# tempmontoring.net
KiCad netlist of a schematic drawn in Altium Designer
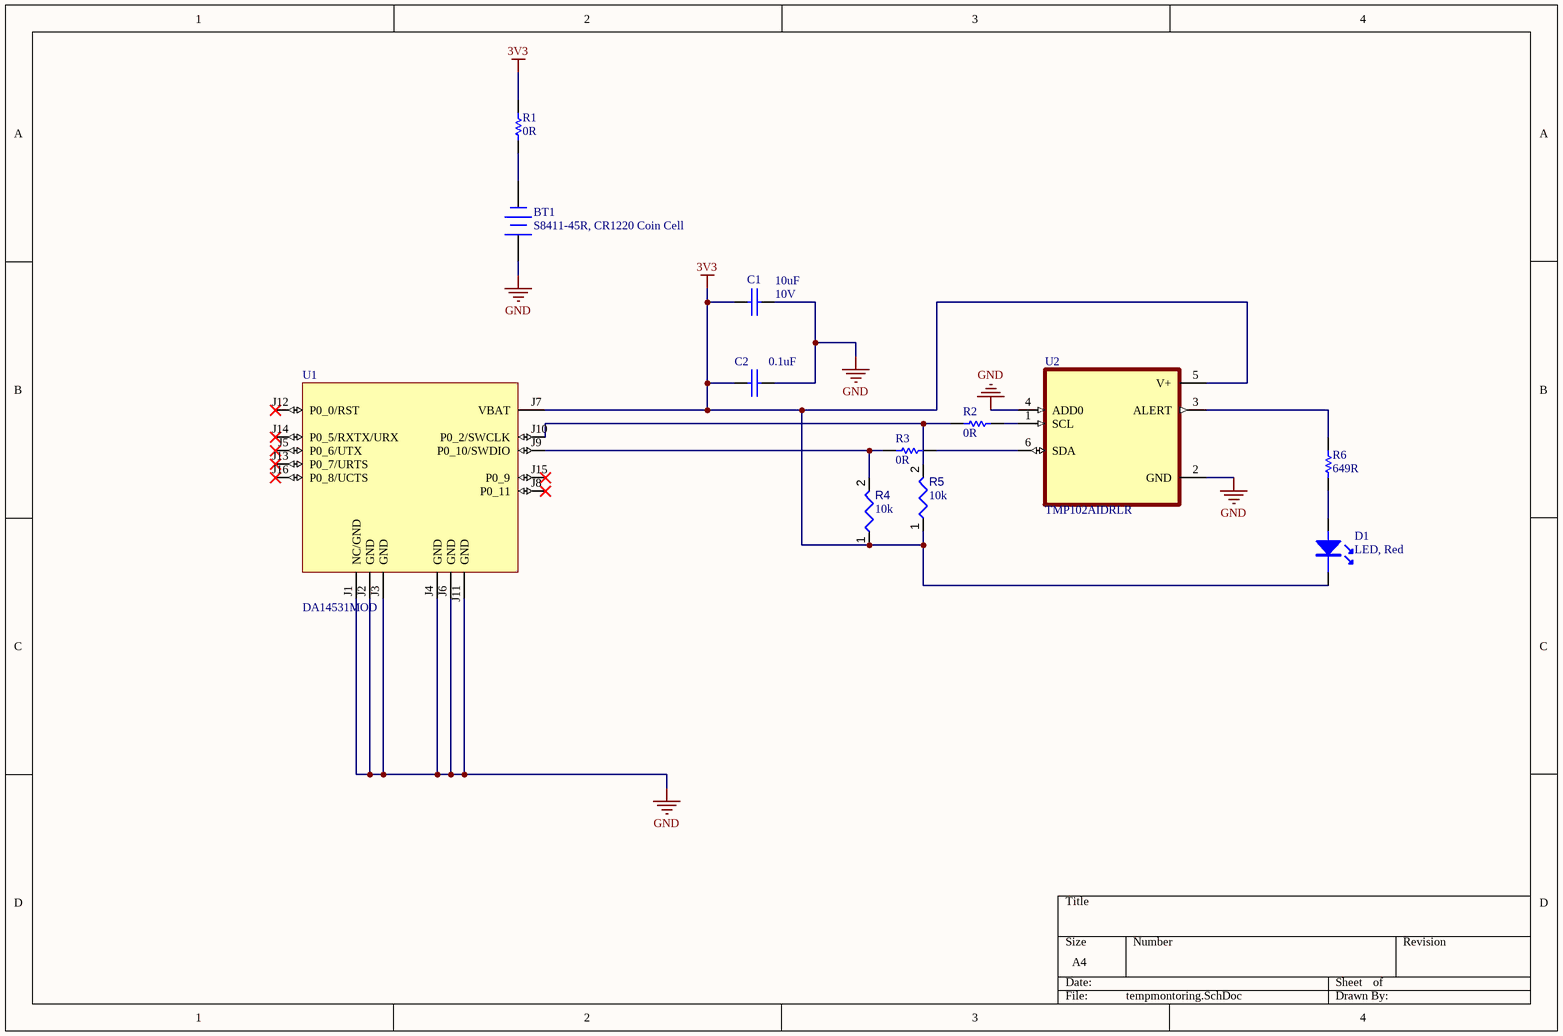
[diagram p0: tempmontoring.SchDoc]

(export (version "E")
  (design (tool "Eeschema 10.0.6"))
  (components
    (comp (ref "BT1")
      (value "S8411-45R, CR1220 Coin Cell")
      (footprint "HWN_S8411-45R")
      (description "Battery Holder, 12 mm Coin Cell, CR1220 SM")
      (fields (field (name "MANUFACTURER'S PART #") "S8411-45R") (field (name "MANUFACTURER") "Harwin"))
      (libsource (lib "Low Power Bluetooth PMOD RevA") (part "BT-S8411-45R-SR-HWN"))
    )
    (comp (ref "C1")
      (value "10uF")
      (footprint "CAPC1608X10N")
      (description "Capacitor, 10uF, 10V, SM")
      (fields
        (field (name "MANUFACTURER'S PART #") "GRM188R61A106KE69D")
        (field (name "MANUFACTURER") "Murata")
        (field (name "VOLTAGE RATING") "10V")
      )
      (libsource (lib "Low Power Bluetooth PMOD RevA") (part "CI-10uF-10V-X5R-SR-MRT"))
    )
    (comp (ref "C2")
      (value "0.1uF")
      (footprint "CAPC1608X09N")
      (description "Capacitor, 0.1uF, 50V, SM")
      (fields
        (field (name "MANUFACTURER'S PART #") "CC0603KRX7R9BB104")
        (field (name "MANUFACTURER") "Yageo")
      )
      (libsource (lib "Low Power Bluetooth PMOD RevA") (part "CI-0.1uF-50V-X7R-SR-YAG"))
    )
    (comp (ref "D1")
      (value "LED, Red")
      (footprint "DIOC2012X08N_WTE")
      (description "LED, Red, 0805 SM")
      (fields
        (field (name "MANUFACTURER'S PART #") "150080RS75000")
        (field (name "MANUFACTURER") "Wurth Elektronik")
      )
      (libsource (lib "Low Power Bluetooth PMOD RevA") (part "DA-150080RS75000-SR-WTE"))
    )
    (comp (ref "R1")
      (value "0R")
      (footprint "RESC1608X06N")
      (description "Resistor, 0 ohms, 1/8W, 1%, SM")
      (fields (field (name "MANUFACTURER'S PART #") "RK73Z1JTTD") (field (name "MANUFACTURER") "KOA Speer"))
      (libsource (lib "Low Power Bluetooth PMOD RevA") (part "RP-0-SR-KOA"))
    )
    (comp (ref "R2")
      (value "0R")
      (footprint "RESC1608X06N")
      (description "Resistor, 0 ohms, 1/8W, 1%, SM")
      (fields (field (name "MANUFACTURER'S PART #") "RK73Z1JTTD") (field (name "MANUFACTURER") "KOA Speer"))
      (libsource (lib "Low Power Bluetooth PMOD RevA") (part "RP-0-SR-KOA"))
    )
    (comp (ref "R3")
      (value "0R")
      (footprint "RESC1608X06N")
      (description "Resistor, 0 ohms, 1/8W, 1%, SM")
      (fields (field (name "MANUFACTURER'S PART #") "RK73Z1JTTD") (field (name "MANUFACTURER") "KOA Speer"))
      (libsource (lib "Low Power Bluetooth PMOD RevA") (part "RP-0-SR-KOA"))
    )
    (comp (ref "R4")
      (value "10k")
      (footprint "RESC0402(1005)_L")
      (description "Chip Resistor, 10 kOhms, +/-1 %, 63 mW, -55 to 125 degC, 0402")
      (fields (field (name "POWER") "63mW") (field (name "TOLERANCE") "1%"))
      (libsource (lib "Indian Institute of Technology Hyderabad-Educator Program") (part "RES-2"))
    )
    (comp (ref "R5")
      (value "10k")
      (footprint "RESC0402(1005)_L")
      (description "Chip Resistor, 10 kOhms, +/-1 %, 63 mW, -55 to 125 degC, 0402")
      (fields (field (name "POWER") "63mW") (field (name "TOLERANCE") "1%"))
      (libsource (lib "Indian Institute of Technology Hyderabad-Educator Program") (part "RES-2"))
    )
    (comp (ref "R6")
      (value "649R")
      (footprint "RESC1608X06N")
      (description "Resistor, 649 ohms, 1/8W, 1%, SM")
      (fields
        (field (name "MANUFACTURER'S PART #") "RK73H1JTTD6490F")
        (field (name "MANUFACTURER") "KOA Speer")
      )
      (libsource (lib "Low Power Bluetooth PMOD RevA") (part "RP-649-SR-KOA"))
    )
    (comp (ref "U1")
      (value "DA14531MOD")
      (footprint "DLG_DA14531MOD-00F01002")
      (description "DA14531MOD, Bluetooth Low Energy 5.1 Module, SM")
      (libsource (lib "Low Power Bluetooth PMOD RevA") (part "UD-DA14531MOD-00F01002-SR-DLG"))
    )
    (comp (ref "U2")
      (value "TMP102AIDRLR")
      (footprint "SOT50P160X60-6N")
      (description "2C digital temperature sensor, I2C/SMBus in 2.56mm2 package")
      (fields (field (name "MF") "Texas Instruments"))
      (libsource (lib "TMP102AIDRLR") (part "TMP102AIDRLR"))
    )
  )
  (nets
    (net (code "1") (name "3V3") (class "Default")
      (node (ref "C1") (pin "1") (pinfunction "1_1") (pintype "passive"))
      (node (ref "C2") (pin "1") (pinfunction "1_1") (pintype "passive"))
      (node (ref "D1") (pin "K") (pintype "passive"))
      (node (ref "R1") (pin "1") (pinfunction "1_1") (pintype "passive"))
      (node (ref "R4") (pin "1") (pinfunction "1_1") (pintype "passive"))
      (node (ref "R5") (pin "1") (pinfunction "1_1") (pintype "passive"))
      (node (ref "U1") (pin "J7") (pinfunction "VBAT_J7") (pintype "power_in"))
      (node (ref "U2") (pin "5") (pinfunction "V+_5") (pintype "power_in"))
    )
    (net (code "2") (name "GND") (class "Default")
      (node (ref "BT1") (pin "1") (pinfunction "+_1") (pintype "passive"))
      (node (ref "C1") (pin "2") (pinfunction "2_2") (pintype "passive"))
      (node (ref "C2") (pin "2") (pinfunction "2_2") (pintype "passive"))
      (node (ref "U1") (pin "J1") (pinfunction "NC/GND_J1") (pintype "power_in"))
      (node (ref "U1") (pin "J11") (pinfunction "GND_J11") (pintype "power_in"))
      (node (ref "U1") (pin "J2") (pinfunction "GND_J2") (pintype "power_in"))
      (node (ref "U1") (pin "J3") (pinfunction "GND_J3") (pintype "power_in"))
      (node (ref "U1") (pin "J4") (pinfunction "GND_J4") (pintype "power_in"))
      (node (ref "U1") (pin "J6") (pinfunction "GND_J6") (pintype "power_in"))
      (node (ref "U2") (pin "2") (pinfunction "GND_2") (pintype "power_in"))
      (node (ref "U2") (pin "4") (pinfunction "ADD0_4") (pintype "input"))
    )
    (net (code "3") (name "Net-(BT1--)") (class "Default")
      (node (ref "BT1") (pin "2") (pinfunction "-_2") (pintype "passive"))
      (node (ref "R1") (pin "2") (pinfunction "2_2") (pintype "passive"))
    )
    (net (code "4") (name "Net-(D1-PadA)") (class "Default")
      (node (ref "D1") (pin "A") (pintype "passive"))
      (node (ref "R6") (pin "2") (pinfunction "2_2") (pintype "passive"))
    )
    (net (code "5") (name "Net-(U1-P0_2{slash}SWCLK)") (class "Default")
      (node (ref "R2") (pin "1") (pinfunction "1_1") (pintype "passive"))
      (node (ref "R5") (pin "2") (pinfunction "2_2") (pintype "passive"))
      (node (ref "U1") (pin "J10") (pinfunction "P0_2/SWCLK_J10") (pintype "bidirectional"))
    )
    (net (code "6") (name "Net-(U1-P0_10{slash}SWDIO)") (class "Default")
      (node (ref "R3") (pin "1") (pinfunction "1_1") (pintype "passive"))
      (node (ref "R4") (pin "2") (pinfunction "2_2") (pintype "passive"))
      (node (ref "U1") (pin "J9") (pinfunction "P0_10/SWDIO_J9") (pintype "bidirectional"))
    )
    (net (code "7") (name "Net-(U2-ALERT)") (class "Default")
      (node (ref "R6") (pin "1") (pinfunction "1_1") (pintype "passive"))
      (node (ref "U2") (pin "3") (pinfunction "ALERT_3") (pintype "output"))
    )
    (net (code "8") (name "Net-(U2-SCL)") (class "Default")
      (node (ref "R2") (pin "2") (pinfunction "2_2") (pintype "passive"))
      (node (ref "U2") (pin "1") (pinfunction "SCL_1") (pintype "input"))
    )
    (net (code "9") (name "Net-(U2-SDA)") (class "Default")
      (node (ref "R3") (pin "2") (pinfunction "2_2") (pintype "passive"))
      (node (ref "U2") (pin "6") (pinfunction "SDA_6") (pintype "bidirectional"))
    )
    (net (code "10") (name "unconnected-(U1-P0_0{slash}RST-PadJ12)") (class "Default")
      (node (ref "U1") (pin "J12") (pinfunction "P0_0/RST_J12") (pintype "bidirectional+no_connect"))
    )
    (net (code "11") (name "unconnected-(U1-P0_5{slash}RXTX{slash}URX-PadJ14)") (class "Default")
      (node (ref "U1") (pin "J14") (pinfunction "P0_5/RXTX/URX_J14") (pintype "bidirectional+no_connect"))
    )
    (net (code "12") (name "unconnected-(U1-P0_6{slash}UTX-PadJ5)") (class "Default")
      (node (ref "U1") (pin "J5") (pinfunction "P0_6/UTX_J5") (pintype "bidirectional+no_connect"))
    )
    (net (code "13") (name "unconnected-(U1-P0_7{slash}URTS-PadJ13)") (class "Default")
      (node (ref "U1") (pin "J13") (pinfunction "P0_7/URTS_J13") (pintype "bidirectional+no_connect"))
    )
    (net (code "14") (name "unconnected-(U1-P0_8{slash}UCTS-PadJ16)") (class "Default")
      (node (ref "U1") (pin "J16") (pinfunction "P0_8/UCTS_J16") (pintype "bidirectional+no_connect"))
    )
    (net (code "15") (name "unconnected-(U1-P0_9-PadJ15)") (class "Default")
      (node (ref "U1") (pin "J15") (pinfunction "P0_9_J15") (pintype "bidirectional+no_connect"))
    )
    (net (code "16") (name "unconnected-(U1-P0_11-PadJ8)") (class "Default")
      (node (ref "U1") (pin "J8") (pinfunction "P0_11_J8") (pintype "bidirectional+no_connect"))
    )
  )
)
